# Sheet2.net
KiCad netlist of a schematic drawn in Altium Designer
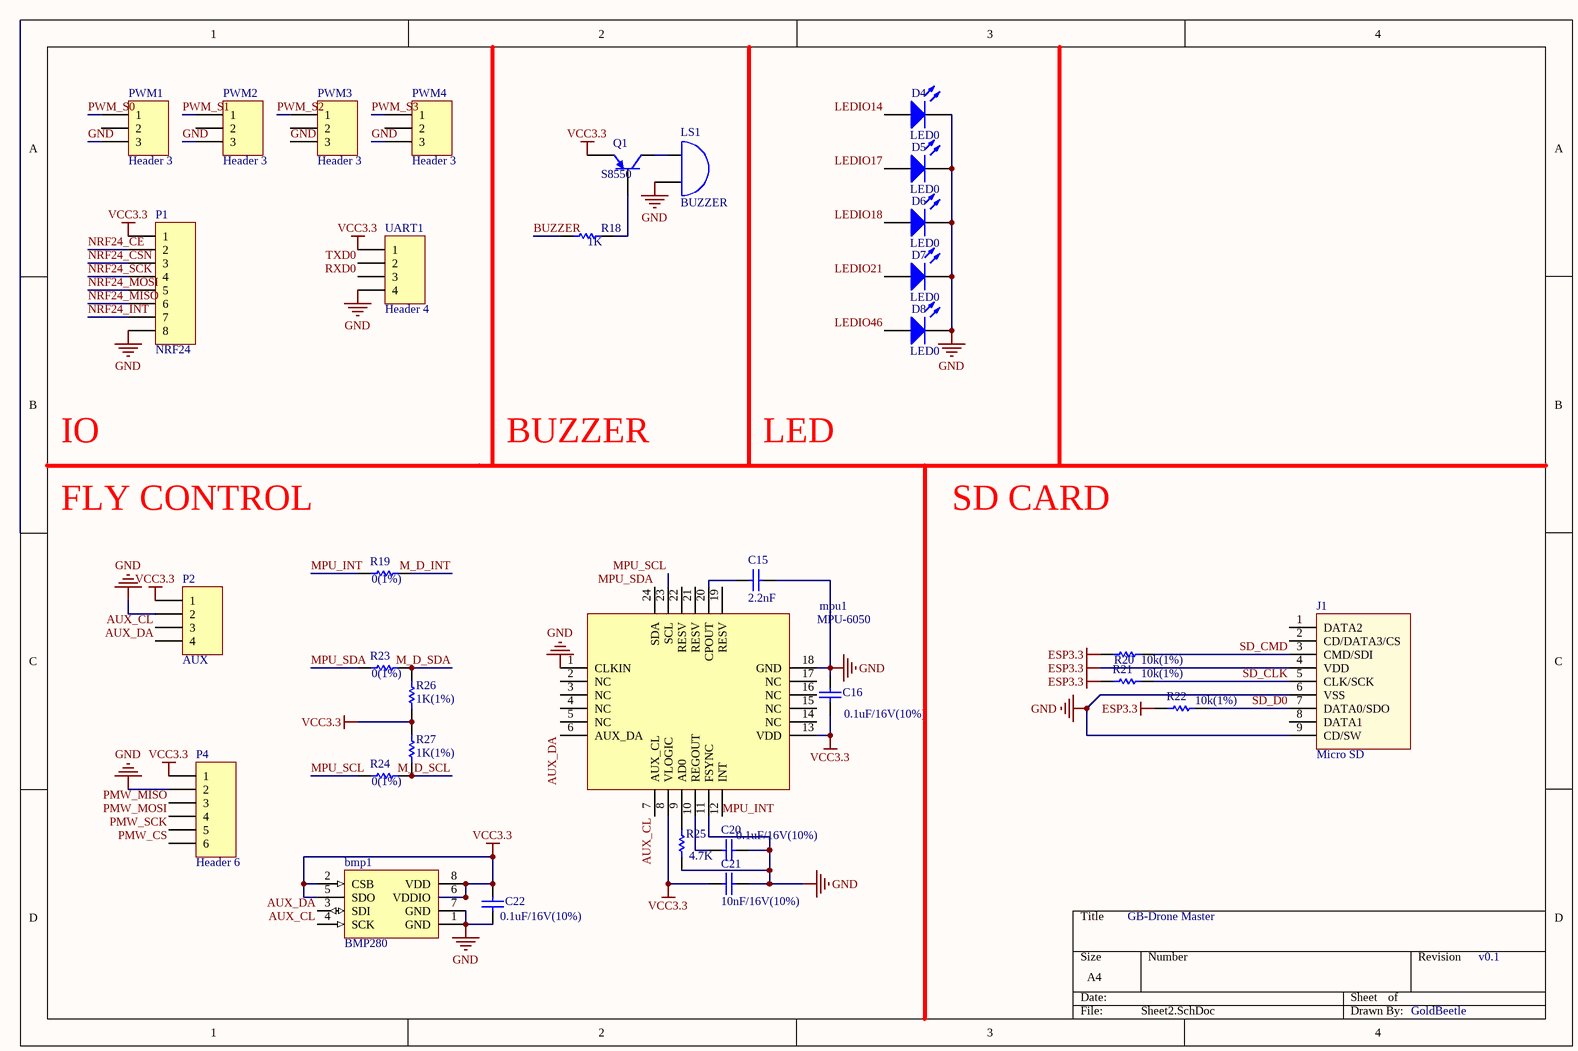
[diagram p0: Sheet2.SchDoc]

(export (version "E")
  (design (tool "Eeschema 10.0.6"))
  (components
    (comp (ref "bmp1")
      (value "BMP280")
      (footprint "BMP280 LGA8")
      (description "气压传感器")
      (libsource (lib "welkin_lib_v1.0") (part "BMP280"))
    )
    (comp (ref "C15")
      (value "2.2nF")
      (footprint "C0805")
      (description "Capacitor")
      (fields (field (name "PUBLISHER") "Altium Limited"))
      (libsource (lib "Miscellaneous Devices") (part "Cap"))
    )
    (comp (ref "C16")
      (value "0.1uF/16V(10%)")
      (footprint "C0805")
      (description "Capacitor")
      (fields (field (name "PUBLISHER") "Altium Limited"))
      (libsource (lib "Miscellaneous Devices") (part "Cap"))
    )
    (comp (ref "C20")
      (value "0.1uF/16V(10%)")
      (footprint "C0805")
      (description "Capacitor")
      (fields (field (name "PUBLISHER") "Altium Limited"))
      (libsource (lib "Miscellaneous Devices") (part "Cap"))
    )
    (comp (ref "C21")
      (value "10nF/16V(10%)")
      (footprint "C0805")
      (description "Capacitor")
      (fields (field (name "PUBLISHER") "Altium Limited"))
      (libsource (lib "Miscellaneous Devices") (part "Cap"))
    )
    (comp (ref "C22")
      (value "0.1uF/16V(10%)")
      (footprint "C0805")
      (description "Capacitor")
      (fields (field (name "PUBLISHER") "Altium Limited"))
      (libsource (lib "Miscellaneous Devices") (part "Cap"))
    )
    (comp (ref "D4")
      (value "LED0")
      (footprint "C0805")
      (description "Typical INFRARED GaAs LED")
      (fields (field (name "PUBLISHER") "Altium Limited"))
      (libsource (lib "Miscellaneous Devices") (part "LED0"))
    )
    (comp (ref "D5")
      (value "LED0")
      (footprint "C0805")
      (description "Typical INFRARED GaAs LED")
      (fields (field (name "PUBLISHER") "Altium Limited"))
      (libsource (lib "Miscellaneous Devices") (part "LED0"))
    )
    (comp (ref "D6")
      (value "LED0")
      (footprint "C0805")
      (description "Typical INFRARED GaAs LED")
      (fields (field (name "PUBLISHER") "Altium Limited"))
      (libsource (lib "Miscellaneous Devices") (part "LED0"))
    )
    (comp (ref "D7")
      (value "LED0")
      (footprint "C0805")
      (description "Typical INFRARED GaAs LED")
      (fields (field (name "PUBLISHER") "Altium Limited"))
      (libsource (lib "Miscellaneous Devices") (part "LED0"))
    )
    (comp (ref "D8")
      (value "LED0")
      (footprint "C0805")
      (description "Typical INFRARED GaAs LED")
      (fields (field (name "PUBLISHER") "Altium Limited"))
      (libsource (lib "Miscellaneous Devices") (part "LED0"))
    )
    (comp (ref "J1")
      (value "Micro SD")
      (footprint "Micro SD")
      (description "Micro SD卡")
      (fields (field (name "版权归属") "源创客"))
      (libsource (lib "welkin_lib_v1.0") (part "Micro SD"))
    )
    (comp (ref "LS1")
      (value "BUZZER")
      (footprint "Beeper")
      (description "Electrical Bell")
      (fields (field (name "PUBLISHER") "Altium Limited"))
      (libsource (lib "Miscellaneous Devices") (part "Bell"))
    )
    (comp (ref "mpu1")
      (value "MPU-6050")
      (footprint "QFN24 4X4_N")
      (description "传感器")
      (libsource (lib "welkin_lib_v1.0") (part "MPU-6050"))
    )
    (comp (ref "P1")
      (value "NRF24")
      (footprint "NRF24_line")
      (description "Header, 8-Pin")
      (fields (field (name "PUBLISHER") "Altium Limited"))
      (libsource (lib "Miscellaneous Connectors") (part "Header 8"))
    )
    (comp (ref "P2")
      (value "AUX")
      (footprint "XH2.54-4P")
      (description "Header, 4-Pin")
      (fields (field (name "PUBLISHER") "Altium Limited"))
      (libsource (lib "Miscellaneous Connectors") (part "Header 4"))
    )
    (comp (ref "P4")
      (value "Header 6")
      (footprint "XH2.54-6P")
      (description "Header, 6-Pin")
      (fields (field (name "PUBLISHER") "Altium Limited"))
      (libsource (lib "Miscellaneous Connectors") (part "Header 6"))
    )
    (comp (ref "PWM1")
      (value "Header 3")
      (footprint "HDR1X3")
      (description "Header, 3-Pin")
      (fields (field (name "PUBLISHER") "Altium Limited"))
      (libsource (lib "Miscellaneous Connectors") (part "Header 3"))
    )
    (comp (ref "PWM2")
      (value "Header 3")
      (footprint "HDR1X3")
      (description "Header, 3-Pin")
      (fields (field (name "PUBLISHER") "Altium Limited"))
      (libsource (lib "Miscellaneous Connectors") (part "Header 3"))
    )
    (comp (ref "PWM3")
      (value "Header 3")
      (footprint "HDR1X3")
      (description "Header, 3-Pin")
      (fields (field (name "PUBLISHER") "Altium Limited"))
      (libsource (lib "Miscellaneous Connectors") (part "Header 3"))
    )
    (comp (ref "PWM4")
      (value "Header 3")
      (footprint "HDR1X3")
      (description "Header, 3-Pin")
      (fields (field (name "PUBLISHER") "Altium Limited"))
      (libsource (lib "Miscellaneous Connectors") (part "Header 3"))
    )
    (comp (ref "Q1")
      (value "S8550")
      (footprint "SOT-23B_N")
      (description "PNP Bipolar Transistor")
      (fields (field (name "PUBLISHER") "Altium Limited"))
      (libsource (lib "Miscellaneous Devices") (part "PNP"))
    )
    (comp (ref "R18")
      (value "1K")
      (footprint "C0805")
      (description "Resistor")
      (fields (field (name "PUBLISHER") "Altium Limited"))
      (libsource (lib "Miscellaneous Devices") (part "Res1"))
    )
    (comp (ref "R19")
      (value "0(1%)")
      (footprint "C0805")
      (description "Resistor")
      (fields (field (name "PUBLISHER") "Altium Limited"))
      (libsource (lib "Miscellaneous Devices") (part "Res1"))
    )
    (comp (ref "R20")
      (value "10k(1%)")
      (footprint "C0805")
      (description "Resistor")
      (fields (field (name "PUBLISHER") "Altium Limited"))
      (libsource (lib "Miscellaneous Devices") (part "Res1"))
    )
    (comp (ref "R21")
      (value "10k(1%)")
      (footprint "C0805")
      (description "Resistor")
      (fields (field (name "PUBLISHER") "Altium Limited"))
      (libsource (lib "Miscellaneous Devices") (part "Res1"))
    )
    (comp (ref "R22")
      (value "10k(1%)")
      (footprint "C0805")
      (description "Resistor")
      (fields (field (name "PUBLISHER") "Altium Limited"))
      (libsource (lib "Miscellaneous Devices") (part "Res1"))
    )
    (comp (ref "R23")
      (value "0(1%)")
      (footprint "C0805")
      (description "Resistor")
      (fields (field (name "PUBLISHER") "Altium Limited"))
      (libsource (lib "Miscellaneous Devices") (part "Res1"))
    )
    (comp (ref "R24")
      (value "0(1%)")
      (footprint "C0805")
      (description "Resistor")
      (fields (field (name "PUBLISHER") "Altium Limited"))
      (libsource (lib "Miscellaneous Devices") (part "Res1"))
    )
    (comp (ref "R25")
      (value "4.7K")
      (footprint "C0805")
      (description "Resistor")
      (fields (field (name "PUBLISHER") "Altium Limited"))
      (libsource (lib "Miscellaneous Devices") (part "Res1"))
    )
    (comp (ref "R26")
      (value "1K(1%)")
      (footprint "C0805")
      (description "Resistor")
      (fields (field (name "PUBLISHER") "Altium Limited"))
      (libsource (lib "Miscellaneous Devices") (part "Res1"))
    )
    (comp (ref "R27")
      (value "1K(1%)")
      (footprint "C0805")
      (description "Resistor")
      (fields (field (name "PUBLISHER") "Altium Limited"))
      (libsource (lib "Miscellaneous Devices") (part "Res1"))
    )
    (comp (ref "UART1")
      (value "Header 4")
      (footprint "HDR1X4")
      (description "Header, 4-Pin")
      (fields (field (name "PUBLISHER") "Altium Limited"))
      (libsource (lib "Miscellaneous Connectors") (part "Header 4"))
    )
  )
  (nets
    (net (code "1") (name "/AUX_CL") (class "Default")
      (node (ref "P2") (pin "3") (pinfunction "3_3") (pintype "passive"))
      (node (ref "bmp1") (pin "4") (pinfunction "SCK_4") (pintype "input"))
      (node (ref "mpu1") (pin "7") (pinfunction "AUX_CL_7") (pintype "passive"))
    )
    (net (code "2") (name "/AUX_DA") (class "Default")
      (node (ref "P2") (pin "4") (pinfunction "4_4") (pintype "passive"))
      (node (ref "bmp1") (pin "3") (pinfunction "SDI_3") (pintype "bidirectional"))
      (node (ref "mpu1") (pin "6") (pinfunction "AUX_DA_6") (pintype "passive"))
    )
    (net (code "3") (name "/BUZZER") (class "Default")
      (node (ref "R18") (pin "1") (pinfunction "1_1") (pintype "passive"))
    )
    (net (code "4") (name "/LEDIO14") (class "Default")
      (node (ref "D4") (pin "1") (pinfunction "A_1") (pintype "passive"))
    )
    (net (code "5") (name "/LEDIO17") (class "Default")
      (node (ref "D5") (pin "1") (pinfunction "A_1") (pintype "passive"))
    )
    (net (code "6") (name "/LEDIO18") (class "Default")
      (node (ref "D6") (pin "1") (pinfunction "A_1") (pintype "passive"))
    )
    (net (code "7") (name "/LEDIO21") (class "Default")
      (node (ref "D7") (pin "1") (pinfunction "A_1") (pintype "passive"))
    )
    (net (code "8") (name "/LEDIO46") (class "Default")
      (node (ref "D8") (pin "1") (pinfunction "A_1") (pintype "passive"))
    )
    (net (code "9") (name "/MPU_INT") (class "Default")
      (node (ref "R19") (pin "1") (pinfunction "1_1") (pintype "passive"))
      (node (ref "mpu1") (pin "12") (pinfunction "INT_12") (pintype "passive"))
    )
    (net (code "10") (name "/MPU_SCL") (class "Default")
      (node (ref "R24") (pin "1") (pinfunction "1_1") (pintype "passive"))
      (node (ref "mpu1") (pin "23") (pinfunction "SCL_23") (pintype "passive"))
    )
    (net (code "11") (name "/MPU_SDA") (class "Default")
      (node (ref "R23") (pin "1") (pinfunction "1_1") (pintype "passive"))
      (node (ref "mpu1") (pin "24") (pinfunction "SDA_24") (pintype "passive"))
    )
    (net (code "12") (name "/M_D_INT") (class "Default")
      (node (ref "R19") (pin "2") (pinfunction "2_2") (pintype "passive"))
    )
    (net (code "13") (name "/M_D_SCL") (class "Default")
      (node (ref "R24") (pin "2") (pinfunction "2_2") (pintype "passive"))
      (node (ref "R27") (pin "1") (pinfunction "1_1") (pintype "passive"))
    )
    (net (code "14") (name "/M_D_SDA") (class "Default")
      (node (ref "R23") (pin "2") (pinfunction "2_2") (pintype "passive"))
      (node (ref "R26") (pin "2") (pinfunction "2_2") (pintype "passive"))
    )
    (net (code "15") (name "/NRF24_CE") (class "Default")
      (node (ref "P1") (pin "2") (pinfunction "2_2") (pintype "passive"))
    )
    (net (code "16") (name "/NRF24_CSN") (class "Default")
      (node (ref "P1") (pin "3") (pinfunction "3_3") (pintype "passive"))
    )
    (net (code "17") (name "/NRF24_INT") (class "Default")
      (node (ref "P1") (pin "7") (pinfunction "7_7") (pintype "passive"))
    )
    (net (code "18") (name "/NRF24_MISO") (class "Default")
      (node (ref "P1") (pin "6") (pinfunction "6_6") (pintype "passive"))
    )
    (net (code "19") (name "/NRF24_MOSI") (class "Default")
      (node (ref "P1") (pin "5") (pinfunction "5_5") (pintype "passive"))
    )
    (net (code "20") (name "/NRF24_SCK") (class "Default")
      (node (ref "P1") (pin "4") (pinfunction "4_4") (pintype "passive"))
    )
    (net (code "21") (name "/PMW_CS") (class "Default")
      (node (ref "P4") (pin "6") (pinfunction "6_6") (pintype "passive"))
    )
    (net (code "22") (name "/PMW_MISO") (class "Default")
      (node (ref "P4") (pin "3") (pinfunction "3_3") (pintype "passive"))
    )
    (net (code "23") (name "/PMW_MOSI") (class "Default")
      (node (ref "P4") (pin "4") (pinfunction "4_4") (pintype "passive"))
    )
    (net (code "24") (name "/PMW_SCK") (class "Default")
      (node (ref "P4") (pin "5") (pinfunction "5_5") (pintype "passive"))
    )
    (net (code "25") (name "/PWM_S0") (class "Default")
      (node (ref "PWM1") (pin "1") (pinfunction "1_1") (pintype "passive"))
    )
    (net (code "26") (name "/PWM_S1") (class "Default")
      (node (ref "PWM2") (pin "1") (pinfunction "1_1") (pintype "passive"))
    )
    (net (code "27") (name "/PWM_S2") (class "Default")
      (node (ref "PWM3") (pin "1") (pinfunction "1_1") (pintype "passive"))
    )
    (net (code "28") (name "/PWM_S3") (class "Default")
      (node (ref "PWM4") (pin "1") (pinfunction "1_1") (pintype "passive"))
    )
    (net (code "29") (name "/RXD0") (class "Default")
      (node (ref "UART1") (pin "3") (pinfunction "3_3") (pintype "passive"))
    )
    (net (code "30") (name "/SD_CLK") (class "Default")
      (node (ref "J1") (pin "5") (pinfunction "CLK/SCK_5") (pintype "passive"))
      (node (ref "R21") (pin "1") (pinfunction "1_1") (pintype "passive"))
    )
    (net (code "31") (name "/SD_CMD") (class "Default")
      (node (ref "J1") (pin "3") (pinfunction "CMD/SDI_3") (pintype "passive"))
      (node (ref "R20") (pin "1") (pinfunction "1_1") (pintype "passive"))
    )
    (net (code "32") (name "/SD_D0") (class "Default")
      (node (ref "J1") (pin "7") (pinfunction "DATA0/SDO_7") (pintype "passive"))
      (node (ref "R22") (pin "1") (pinfunction "1_1") (pintype "passive"))
    )
    (net (code "33") (name "/TXD0") (class "Default")
      (node (ref "UART1") (pin "2") (pinfunction "2_2") (pintype "passive"))
    )
    (net (code "34") (name "ESP3.3") (class "Default")
      (node (ref "J1") (pin "4") (pinfunction "VDD_4") (pintype "passive"))
      (node (ref "R20") (pin "2") (pinfunction "2_2") (pintype "passive"))
      (node (ref "R21") (pin "2") (pinfunction "2_2") (pintype "passive"))
      (node (ref "R22") (pin "2") (pinfunction "2_2") (pintype "passive"))
    )
    (net (code "35") (name "GND") (class "Default")
      (node (ref "C15") (pin "1") (pinfunction "1_1") (pintype "passive"))
      (node (ref "C16") (pin "1") (pinfunction "1_1") (pintype "passive"))
      (node (ref "C20") (pin "1") (pinfunction "1_1") (pintype "passive"))
      (node (ref "C21") (pin "1") (pinfunction "1_1") (pintype "passive"))
      (node (ref "C22") (pin "2") (pinfunction "2_2") (pintype "passive"))
      (node (ref "D4") (pin "2") (pinfunction "K_2") (pintype "passive"))
      (node (ref "D5") (pin "2") (pinfunction "K_2") (pintype "passive"))
      (node (ref "D6") (pin "2") (pinfunction "K_2") (pintype "passive"))
      (node (ref "D7") (pin "2") (pinfunction "K_2") (pintype "passive"))
      (node (ref "D8") (pin "2") (pinfunction "K_2") (pintype "passive"))
      (node (ref "J1") (pin "6") (pinfunction "VSS_6") (pintype "passive"))
      (node (ref "J1") (pin "9") (pinfunction "CD/SW_9") (pintype "passive"))
      (node (ref "LS1") (pin "2") (pinfunction "B_2") (pintype "passive"))
      (node (ref "P1") (pin "8") (pinfunction "8_8") (pintype "passive"))
      (node (ref "P2") (pin "2") (pinfunction "2_2") (pintype "passive"))
      (node (ref "P4") (pin "2") (pinfunction "2_2") (pintype "passive"))
      (node (ref "PWM1") (pin "3") (pinfunction "3_3") (pintype "passive"))
      (node (ref "PWM2") (pin "3") (pinfunction "3_3") (pintype "passive"))
      (node (ref "PWM3") (pin "3") (pinfunction "3_3") (pintype "passive"))
      (node (ref "PWM4") (pin "3") (pinfunction "3_3") (pintype "passive"))
      (node (ref "R25") (pin "2") (pinfunction "2_2") (pintype "passive"))
      (node (ref "UART1") (pin "4") (pinfunction "4_4") (pintype "passive"))
      (node (ref "bmp1") (pin "1") (pinfunction "GND_1") (pintype "passive"))
      (node (ref "bmp1") (pin "7") (pinfunction "GND_7") (pintype "power_in"))
      (node (ref "mpu1") (pin "1") (pinfunction "CLKIN_1") (pintype "passive"))
      (node (ref "mpu1") (pin "11") (pinfunction "FSYNC_11") (pintype "passive"))
      (node (ref "mpu1") (pin "18") (pinfunction "GND_18") (pintype "passive"))
    )
    (net (code "36") (name "Net-(LS1-A)") (class "Default")
      (node (ref "LS1") (pin "1") (pinfunction "A_1") (pintype "passive"))
      (node (ref "Q1") (pin "3") (pinfunction "C_3") (pintype "passive"))
    )
    (net (code "37") (name "Net-(Q1-B)") (class "Default")
      (node (ref "Q1") (pin "1") (pinfunction "B_1") (pintype "passive"))
      (node (ref "R18") (pin "2") (pinfunction "2_2") (pintype "passive"))
    )
    (net (code "38") (name "Net-(mpu1-AD0)") (class "Default")
      (node (ref "R25") (pin "1") (pinfunction "1_1") (pintype "passive"))
      (node (ref "mpu1") (pin "9") (pinfunction "AD0_9") (pintype "passive"))
    )
    (net (code "39") (name "Net-(mpu1-CPOUT)") (class "Default")
      (node (ref "C15") (pin "2") (pinfunction "2_2") (pintype "passive"))
      (node (ref "mpu1") (pin "20") (pinfunction "CPOUT_20") (pintype "passive"))
    )
    (net (code "40") (name "Net-(mpu1-REGOUT)") (class "Default")
      (node (ref "C20") (pin "2") (pinfunction "2_2") (pintype "passive"))
      (node (ref "mpu1") (pin "10") (pinfunction "REGOUT_10") (pintype "passive"))
    )
    (net (code "41") (name "VCC3.3") (class "Default")
      (node (ref "C16") (pin "2") (pinfunction "2_2") (pintype "passive"))
      (node (ref "C21") (pin "2") (pinfunction "2_2") (pintype "passive"))
      (node (ref "C22") (pin "1") (pinfunction "1_1") (pintype "passive"))
      (node (ref "P1") (pin "1") (pinfunction "1_1") (pintype "passive"))
      (node (ref "P2") (pin "1") (pinfunction "1_1") (pintype "passive"))
      (node (ref "P4") (pin "1") (pinfunction "1_1") (pintype "passive"))
      (node (ref "Q1") (pin "2") (pinfunction "E_2") (pintype "passive"))
      (node (ref "R26") (pin "1") (pinfunction "1_1") (pintype "passive"))
      (node (ref "R27") (pin "2") (pinfunction "2_2") (pintype "passive"))
      (node (ref "UART1") (pin "1") (pinfunction "1_1") (pintype "passive"))
      (node (ref "bmp1") (pin "2") (pinfunction "CSB_2") (pintype "input"))
      (node (ref "bmp1") (pin "5") (pinfunction "SDO_5") (pintype "power_in"))
      (node (ref "bmp1") (pin "6") (pinfunction "VDDIO_6") (pintype "power_in"))
      (node (ref "bmp1") (pin "8") (pinfunction "VDD_8") (pintype "power_in"))
      (node (ref "mpu1") (pin "13") (pinfunction "VDD_13") (pintype "passive"))
      (node (ref "mpu1") (pin "8") (pinfunction "VLOGIC_8") (pintype "passive"))
    )
    (net (code "42") (name "unconnected-(J1-CD{slash}DATA3{slash}CS-Pad2)") (class "Default")
      (node (ref "J1") (pin "2") (pinfunction "CD/DATA3/CS_2") (pintype "passive"))
    )
    (net (code "43") (name "unconnected-(J1-DATA1-Pad8)") (class "Default")
      (node (ref "J1") (pin "8") (pinfunction "DATA1_8") (pintype "passive"))
    )
    (net (code "44") (name "unconnected-(J1-DATA2-Pad1)") (class "Default")
      (node (ref "J1") (pin "1") (pinfunction "DATA2_1") (pintype "passive"))
    )
    (net (code "45") (name "unconnected-(PWM1-Pad2)") (class "Default")
      (node (ref "PWM1") (pin "2") (pinfunction "2_2") (pintype "passive"))
    )
    (net (code "46") (name "unconnected-(PWM2-Pad2)") (class "Default")
      (node (ref "PWM2") (pin "2") (pinfunction "2_2") (pintype "passive"))
    )
    (net (code "47") (name "unconnected-(PWM3-Pad2)") (class "Default")
      (node (ref "PWM3") (pin "2") (pinfunction "2_2") (pintype "passive"))
    )
    (net (code "48") (name "unconnected-(PWM4-Pad2)") (class "Default")
      (node (ref "PWM4") (pin "2") (pinfunction "2_2") (pintype "passive"))
    )
    (net (code "49") (name "unconnected-(mpu1-NC-Pad2)") (class "Default")
      (node (ref "mpu1") (pin "2") (pinfunction "NC_2") (pintype "passive"))
    )
    (net (code "50") (name "unconnected-(mpu1-NC-Pad3)") (class "Default")
      (node (ref "mpu1") (pin "3") (pinfunction "NC_3") (pintype "passive"))
    )
    (net (code "51") (name "unconnected-(mpu1-NC-Pad4)") (class "Default")
      (node (ref "mpu1") (pin "4") (pinfunction "NC_4") (pintype "passive"))
    )
    (net (code "52") (name "unconnected-(mpu1-NC-Pad5)") (class "Default")
      (node (ref "mpu1") (pin "5") (pinfunction "NC_5") (pintype "passive"))
    )
    (net (code "53") (name "unconnected-(mpu1-NC-Pad14)") (class "Default")
      (node (ref "mpu1") (pin "14") (pinfunction "NC_14") (pintype "passive"))
    )
    (net (code "54") (name "unconnected-(mpu1-NC-Pad15)") (class "Default")
      (node (ref "mpu1") (pin "15") (pinfunction "NC_15") (pintype "passive"))
    )
    (net (code "55") (name "unconnected-(mpu1-NC-Pad16)") (class "Default")
      (node (ref "mpu1") (pin "16") (pinfunction "NC_16") (pintype "passive"))
    )
    (net (code "56") (name "unconnected-(mpu1-NC-Pad17)") (class "Default")
      (node (ref "mpu1") (pin "17") (pinfunction "NC_17") (pintype "passive"))
    )
    (net (code "57") (name "unconnected-(mpu1-RESV-Pad19)") (class "Default")
      (node (ref "mpu1") (pin "19") (pinfunction "RESV_19") (pintype "passive"))
    )
    (net (code "58") (name "unconnected-(mpu1-RESV-Pad21)") (class "Default")
      (node (ref "mpu1") (pin "21") (pinfunction "RESV_21") (pintype "passive"))
    )
    (net (code "59") (name "unconnected-(mpu1-RESV-Pad22)") (class "Default")
      (node (ref "mpu1") (pin "22") (pinfunction "RESV_22") (pintype "passive"))
    )
  )
)
